# MCU.net
KiCad netlist of a schematic drawn in Altium Designer
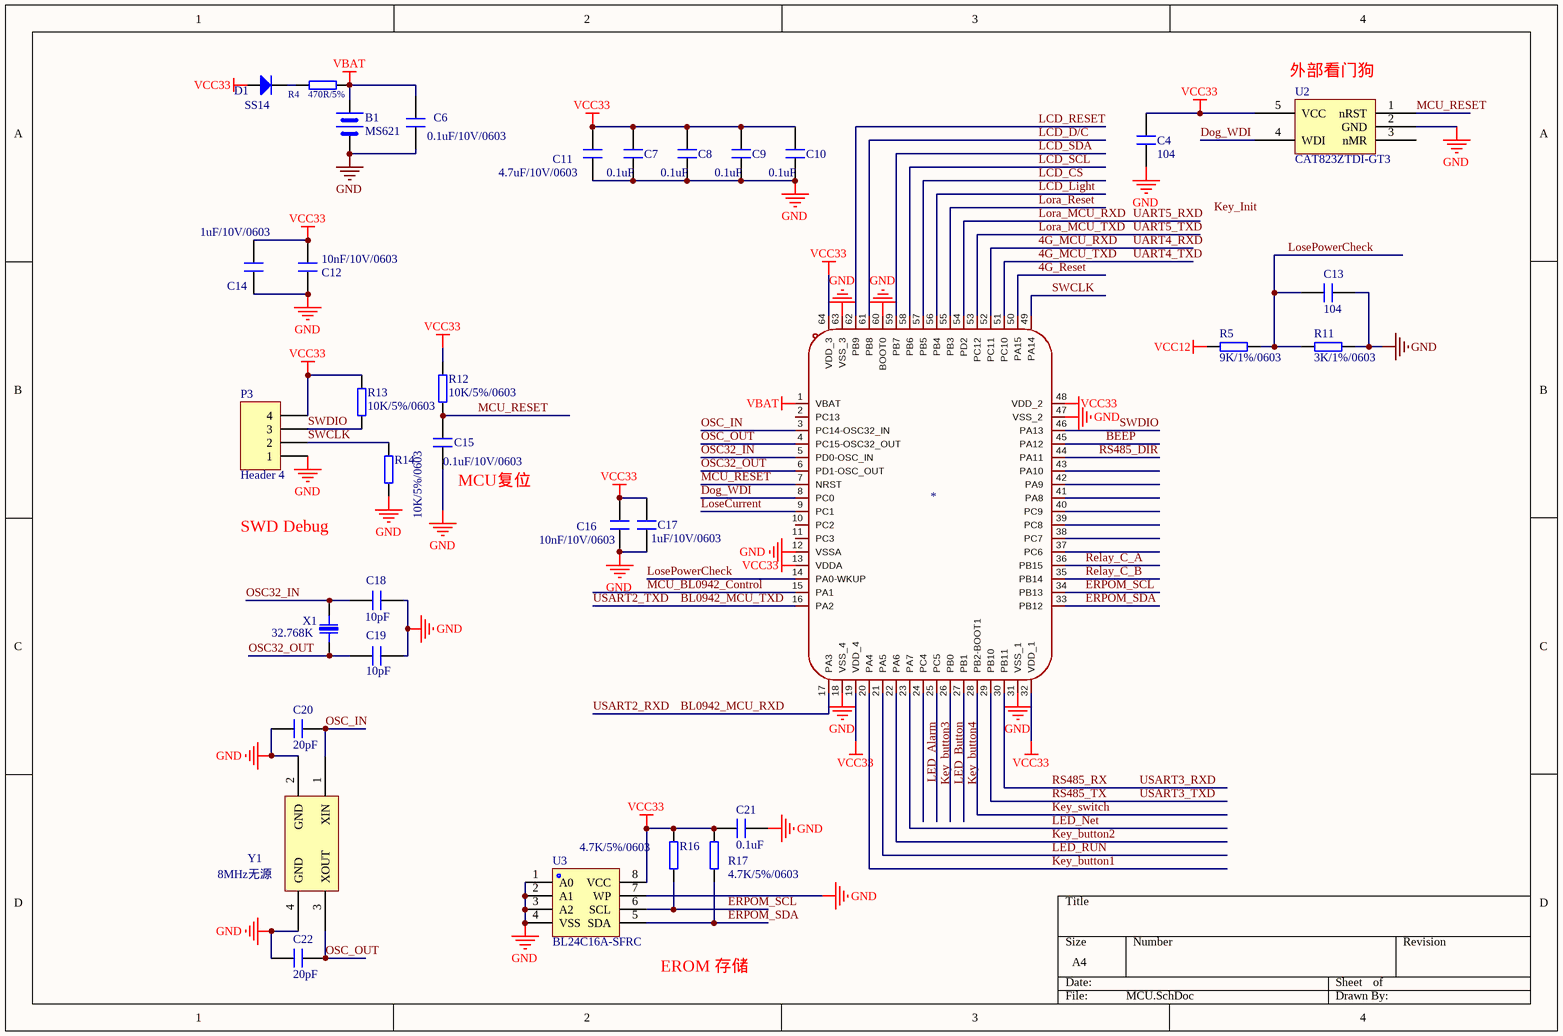
[diagram p0: MCU.SchDoc]

(export (version "E")
  (design (tool "Eeschema 10.0.6"))
  (components
    (comp (ref "B1") (value "MS621") (footprint "MS621") (libsource (lib "ES_Schematic") (part "BATTERY")))
    (comp (ref "C4") (value "104") (footprint "0603R") (libsource (lib "ES_Schematic") (part "CAP")))
    (comp (ref "C6")
      (value "0.1uF/10V/0603")
      (footprint "0603R")
      (libsource (lib "ES_Schematic") (part "CAP_1"))
    )
    (comp (ref "C7") (value "0.1uF") (footprint "0603R") (libsource (lib "ES_Schematic") (part "CAP_1")))
    (comp (ref "C8") (value "0.1uF") (footprint "0603R") (libsource (lib "ES_Schematic") (part "CAP_1")))
    (comp (ref "C9") (value "0.1uF") (footprint "0603R") (libsource (lib "ES_Schematic") (part "CAP_1")))
    (comp (ref "C10") (value "0.1uF") (footprint "0603R") (libsource (lib "ES_Schematic") (part "CAP_1")))
    (comp (ref "C11")
      (value "4.7uF/10V/0603")
      (footprint "0603R")
      (libsource (lib "ES_Schematic") (part "CAP_1"))
    )
    (comp (ref "C12")
      (value "10nF/10V/0603")
      (footprint "0603R")
      (libsource (lib "ES_Schematic") (part "CAP_1"))
    )
    (comp (ref "C13") (value "104") (footprint "0603R") (libsource (lib "ES_Schematic") (part "CAP")))
    (comp (ref "C14")
      (value "1uF/10V/0603")
      (footprint "0603R")
      (libsource (lib "ES_Schematic") (part "CAP_1"))
    )
    (comp (ref "C15")
      (value "0.1uF/10V/0603")
      (footprint "0603R")
      (libsource (lib "ES_Schematic") (part "CAP_1"))
    )
    (comp (ref "C16")
      (value "10nF/10V/0603")
      (footprint "0603R")
      (libsource (lib "ES_Schematic") (part "CAP_1"))
    )
    (comp (ref "C17")
      (value "1uF/10V/0603")
      (footprint "0603R")
      (libsource (lib "ES_Schematic") (part "CAP_1"))
    )
    (comp (ref "C18") (value "10pF") (footprint "0603r") (libsource (lib "ES_Schematic") (part "CAP")))
    (comp (ref "C19") (value "10pF") (footprint "0603r") (libsource (lib "ES_Schematic") (part "CAP")))
    (comp (ref "C20") (value "20pF") (footprint "0603r") (libsource (lib "ES_Schematic") (part "CAP")))
    (comp (ref "C21") (value "0.1uF") (footprint "0603R") (libsource (lib "ES_Schematic") (part "CAP_1")))
    (comp (ref "C22") (value "20pF") (footprint "0603r") (libsource (lib "ES_Schematic") (part "CAP")))
    (comp (ref "D1") (value "SS14") (footprint "SOD323") (libsource (lib "ES_Schematic") (part "DIODE")))
    (comp (ref "P3")
      (value "Header 4")
      (footprint "HDR1X4")
      (description "Header, 4-Pin")
      (fields (field (name "PUBLISHER") "Altium Limited"))
      (libsource (lib "Miscellaneous Connectors") (part "Header 4"))
    )
    (comp (ref "R4") (value "470R/5%") (footprint "0603R") (libsource (lib "ES_Schematic") (part "RES")))
    (comp (ref "R5") (value "9K/1%/0603") (footprint "0603R") (libsource (lib "ES_Schematic") (part "RES")))
    (comp (ref "R11") (value "3K/1%/0603") (footprint "0603R") (libsource (lib "ES_Schematic") (part "RES")))
    (comp (ref "R12") (value "10K/5%/0603") (footprint "0603r") (libsource (lib "ES_Schematic") (part "RES")))
    (comp (ref "R13") (value "10K/5%/0603") (footprint "0603r") (libsource (lib "ES_Schematic") (part "RES")))
    (comp (ref "R14") (value "10K/5%/0603") (footprint "0603r") (libsource (lib "ES_Schematic") (part "RES")))
    (comp (ref "R16")
      (value "4.7K/5%/0603")
      (footprint "0603R")
      (libsource (lib "ES_Schematic") (part "RES"))
    )
    (comp (ref "R17")
      (value "4.7K/5%/0603")
      (footprint "0603R")
      (libsource (lib "ES_Schematic") (part "RES"))
    )
    (comp (ref "U1")
      (value "*")
      (footprint "LQFP64")
      (libsource (lib "altium-import") (part "root_0_N32G452REL7_"))
    )
    (comp (ref "U2")
      (value "CAT823ZTDI-GT3")
      (footprint "SOT-23-5")
      (libsource (lib "ES_Schematic") (part "CAT823"))
    )
    (comp (ref "U3")
      (value "BL24C16A-SFRC")
      (footprint "TSSOP8")
      (libsource (lib "ES_Schematic") (part "24LC02"))
    )
    (comp (ref "X1")
      (value "32.768K")
      (footprint "无源32.768K晶振圆柱")
      (libsource (lib "ES_Schematic") (part "XTAL"))
    )
    (comp (ref "Y1") (value "8MHz无源") (footprint "3225") (libsource (lib "others") (part "12MHz无源")))
  )
  (nets
    (net (code "1") (name "/4G_MCU_RXD") (class "Default")
      (node (ref "U1") (pin "52") (pinfunction "PC11_52") (pintype "passive"))
    )
    (net (code "2") (name "/4G_MCU_TXD") (class "Default")
      (node (ref "U1") (pin "51") (pinfunction "PC10_51") (pintype "passive"))
    )
    (net (code "3") (name "/4G_Reset") (class "Default")
      (node (ref "U1") (pin "50") (pinfunction "PA15_50") (pintype "passive"))
    )
    (net (code "4") (name "/BEEP") (class "Default")
      (node (ref "U1") (pin "45") (pinfunction "PA12_45") (pintype "passive"))
    )
    (net (code "5") (name "/BL0942_MCU_RXD") (class "Default")
      (node (ref "U1") (pin "17") (pinfunction "PA3_17") (pintype "passive"))
    )
    (net (code "6") (name "/BL0942_MCU_TXD") (class "Default")
      (node (ref "U1") (pin "16") (pinfunction "PA2_16") (pintype "passive"))
    )
    (net (code "7") (name "/Dog_WDI") (class "Default")
      (node (ref "U1") (pin "8") (pinfunction "PC0_8") (pintype "passive"))
      (node (ref "U2") (pin "4") (pinfunction "WDI_4") (pintype "passive"))
    )
    (net (code "8") (name "/ERPOM_SCL") (class "Default")
      (node (ref "R16") (pin "2") (pinfunction "2_2") (pintype "passive"))
      (node (ref "U1") (pin "34") (pinfunction "PB13_34") (pintype "passive"))
      (node (ref "U3") (pin "6") (pinfunction "SCL_6") (pintype "passive"))
    )
    (net (code "9") (name "/ERPOM_SDA") (class "Default")
      (node (ref "R17") (pin "2") (pinfunction "2_2") (pintype "passive"))
      (node (ref "U1") (pin "33") (pinfunction "PB12_33") (pintype "passive"))
      (node (ref "U3") (pin "5") (pinfunction "SDA_5") (pintype "passive"))
    )
    (net (code "11") (name "/Key_button1") (class "Default")
      (node (ref "U1") (pin "20") (pinfunction "PA4_20") (pintype "passive"))
    )
    (net (code "12") (name "/Key_button2") (class "Default")
      (node (ref "U1") (pin "22") (pinfunction "PA6_22") (pintype "passive"))
    )
    (net (code "13") (name "/Key_button3") (class "Default")
      (node (ref "U1") (pin "25") (pinfunction "PC5_25") (pintype "passive"))
    )
    (net (code "14") (name "/Key_button4") (class "Default")
      (node (ref "U1") (pin "27") (pinfunction "PB1_27") (pintype "passive"))
    )
    (net (code "15") (name "/Key_switch") (class "Default")
      (node (ref "U1") (pin "28") (pinfunction "PB2-BOOT1_28") (pintype "passive"))
    )
    (net (code "16") (name "/LCD_CS") (class "Default")
      (node (ref "U1") (pin "57") (pinfunction "PB5_57") (pintype "passive"))
    )
    (net (code "17") (name "/LCD_D{slash}C") (class "Default")
      (node (ref "U1") (pin "61") (pinfunction "PB8_61") (pintype "passive"))
    )
    (net (code "18") (name "/LCD_Light") (class "Default")
      (node (ref "U1") (pin "56") (pinfunction "PB4_56") (pintype "passive"))
    )
    (net (code "19") (name "/LCD_RESET") (class "Default")
      (node (ref "U1") (pin "62") (pinfunction "PB9_62") (pintype "passive"))
    )
    (net (code "20") (name "/LCD_SCL") (class "Default")
      (node (ref "U1") (pin "58") (pinfunction "PB6_58") (pintype "passive"))
    )
    (net (code "21") (name "/LCD_SDA") (class "Default")
      (node (ref "U1") (pin "59") (pinfunction "PB7_59") (pintype "passive"))
    )
    (net (code "22") (name "/LED_Alarm") (class "Default")
      (node (ref "U1") (pin "24") (pinfunction "PC4_24") (pintype "passive"))
    )
    (net (code "23") (name "/LED_Button") (class "Default")
      (node (ref "U1") (pin "26") (pinfunction "PB0_26") (pintype "passive"))
    )
    (net (code "24") (name "/LED_Net") (class "Default")
      (node (ref "U1") (pin "23") (pinfunction "PA7_23") (pintype "passive"))
    )
    (net (code "25") (name "/LED_RUN") (class "Default")
      (node (ref "U1") (pin "21") (pinfunction "PA5_21") (pintype "passive"))
    )
    (net (code "26") (name "/Lora_MCU_RXD") (class "Default")
      (node (ref "U1") (pin "54") (pinfunction "PD2_54") (pintype "passive"))
    )
    (net (code "27") (name "/Lora_MCU_TXD") (class "Default")
      (node (ref "U1") (pin "53") (pinfunction "PC12_53") (pintype "passive"))
    )
    (net (code "28") (name "/Lora_Reset") (class "Default")
      (node (ref "U1") (pin "55") (pinfunction "PB3_55") (pintype "passive"))
    )
    (net (code "29") (name "/LoseCurrent") (class "Default")
      (node (ref "U1") (pin "9") (pinfunction "PC1_9") (pintype "passive"))
    )
    (net (code "30") (name "/LosePowerCheck") (class "Default")
      (node (ref "C13") (pin "2") (pinfunction "2_2") (pintype "passive"))
      (node (ref "R11") (pin "2") (pinfunction "2_2") (pintype "passive"))
      (node (ref "R5") (pin "2") (pinfunction "2_2") (pintype "passive"))
      (node (ref "U1") (pin "14") (pinfunction "PA0-WKUP_14") (pintype "passive"))
    )
    (net (code "31") (name "/MCU_BL0942_Control") (class "Default")
      (node (ref "U1") (pin "15") (pinfunction "PA1_15") (pintype "passive"))
    )
    (net (code "32") (name "/MCU_RESET") (class "Default")
      (node (ref "C15") (pin "2") (pinfunction "2_2") (pintype "passive"))
      (node (ref "R12") (pin "1") (pinfunction "1_1") (pintype "passive"))
      (node (ref "U1") (pin "7") (pinfunction "NRST_7") (pintype "passive"))
      (node (ref "U2") (pin "1") (pinfunction "nRST_1") (pintype "passive"))
    )
    (net (code "33") (name "/OSC32_IN") (class "Default")
      (node (ref "C18") (pin "1") (pinfunction "1_1") (pintype "passive"))
      (node (ref "U1") (pin "5") (pinfunction "PD0-OSC_IN_5") (pintype "passive"))
      (node (ref "X1") (pin "2") (pinfunction "2_2") (pintype "passive"))
    )
    (net (code "34") (name "/OSC32_OUT") (class "Default")
      (node (ref "C19") (pin "2") (pinfunction "2_2") (pintype "passive"))
      (node (ref "U1") (pin "6") (pinfunction "PD1-OSC_OUT_6") (pintype "passive"))
      (node (ref "X1") (pin "1") (pinfunction "1_1") (pintype "passive"))
    )
    (net (code "35") (name "/OSC_IN") (class "Default")
      (node (ref "C20") (pin "2") (pinfunction "2_2") (pintype "passive"))
      (node (ref "U1") (pin "3") (pinfunction "PC14-OSC32_IN_3") (pintype "passive"))
      (node (ref "Y1") (pin "1") (pinfunction "XIN_1") (pintype "passive"))
    )
    (net (code "36") (name "/OSC_OUT") (class "Default")
      (node (ref "C22") (pin "2") (pinfunction "2_2") (pintype "passive"))
      (node (ref "U1") (pin "4") (pinfunction "PC15-OSC32_OUT_4") (pintype "passive"))
      (node (ref "Y1") (pin "3") (pinfunction "XOUT_3") (pintype "passive"))
    )
    (net (code "37") (name "/RS485_DIR") (class "Default")
      (node (ref "U1") (pin "44") (pinfunction "PA11_44") (pintype "passive"))
    )
    (net (code "38") (name "/RS485_RX") (class "Default")
      (node (ref "U1") (pin "30") (pinfunction "PB11_30") (pintype "passive"))
    )
    (net (code "39") (name "/RS485_TX") (class "Default")
      (node (ref "U1") (pin "29") (pinfunction "PB10_29") (pintype "passive"))
    )
    (net (code "40") (name "/Relay_C_A") (class "Default")
      (node (ref "U1") (pin "36") (pinfunction "PB15_36") (pintype "passive"))
    )
    (net (code "41") (name "/Relay_C_B") (class "Default")
      (node (ref "U1") (pin "35") (pinfunction "PB14_35") (pintype "passive"))
    )
    (net (code "42") (name "/SWCLK") (class "Default")
      (node (ref "P3") (pin "2") (pinfunction "2_2") (pintype "passive"))
      (node (ref "R14") (pin "2") (pinfunction "2_2") (pintype "passive"))
      (node (ref "U1") (pin "49") (pinfunction "PA14_49") (pintype "passive"))
    )
    (net (code "43") (name "/SWDIO") (class "Default")
      (node (ref "P3") (pin "3") (pinfunction "3_3") (pintype "passive"))
      (node (ref "R13") (pin "1") (pinfunction "1_1") (pintype "passive"))
      (node (ref "U1") (pin "46") (pinfunction "PA13_46") (pintype "passive"))
    )
    (net (code "44") (name "GND") (class "Default")
      (node (ref "B1") (pin "2") (pinfunction "2_2") (pintype "passive"))
      (node (ref "C10") (pin "1") (pinfunction "1_1") (pintype "passive"))
      (node (ref "C11") (pin "1") (pinfunction "1_1") (pintype "passive"))
      (node (ref "C12") (pin "1") (pinfunction "1_1") (pintype "passive"))
      (node (ref "C13") (pin "1") (pinfunction "1_1") (pintype "passive"))
      (node (ref "C14") (pin "1") (pinfunction "1_1") (pintype "passive"))
      (node (ref "C15") (pin "1") (pinfunction "1_1") (pintype "passive"))
      (node (ref "C16") (pin "1") (pinfunction "1_1") (pintype "passive"))
      (node (ref "C17") (pin "1") (pinfunction "1_1") (pintype "passive"))
      (node (ref "C18") (pin "2") (pinfunction "2_2") (pintype "passive"))
      (node (ref "C19") (pin "1") (pinfunction "1_1") (pintype "passive"))
      (node (ref "C20") (pin "1") (pinfunction "1_1") (pintype "passive"))
      (node (ref "C21") (pin "1") (pinfunction "1_1") (pintype "passive"))
      (node (ref "C22") (pin "1") (pinfunction "1_1") (pintype "passive"))
      (node (ref "C4") (pin "1") (pinfunction "1_1") (pintype "passive"))
      (node (ref "C6") (pin "1") (pinfunction "1_1") (pintype "passive"))
      (node (ref "C7") (pin "1") (pinfunction "1_1") (pintype "passive"))
      (node (ref "C8") (pin "1") (pinfunction "1_1") (pintype "passive"))
      (node (ref "C9") (pin "1") (pinfunction "1_1") (pintype "passive"))
      (node (ref "P3") (pin "1") (pinfunction "1_1") (pintype "passive"))
      (node (ref "R11") (pin "1") (pinfunction "1_1") (pintype "passive"))
      (node (ref "R14") (pin "1") (pinfunction "1_1") (pintype "passive"))
      (node (ref "U1") (pin "12") (pinfunction "VSSA_12") (pintype "passive"))
      (node (ref "U1") (pin "18") (pinfunction "VSS_4_18") (pintype "passive"))
      (node (ref "U1") (pin "31") (pinfunction "VSS_1_31") (pintype "passive"))
      (node (ref "U1") (pin "47") (pinfunction "VSS_2_47") (pintype "passive"))
      (node (ref "U1") (pin "60") (pinfunction "BOOT0_60") (pintype "passive"))
      (node (ref "U1") (pin "63") (pinfunction "VSS_3_63") (pintype "passive"))
      (node (ref "U2") (pin "2") (pinfunction "GND_2") (pintype "passive"))
      (node (ref "U3") (pin "1") (pinfunction "A0_1") (pintype "passive"))
      (node (ref "U3") (pin "2") (pinfunction "A1_2") (pintype "passive"))
      (node (ref "U3") (pin "3") (pinfunction "A2_3") (pintype "passive"))
      (node (ref "U3") (pin "4") (pinfunction "VSS_4") (pintype "passive"))
      (node (ref "U3") (pin "7") (pinfunction "WP_7") (pintype "passive"))
      (node (ref "Y1") (pin "2") (pinfunction "GND_2") (pintype "passive"))
      (node (ref "Y1") (pin "4") (pinfunction "GND_4") (pintype "passive"))
    )
    (net (code "45") (name "Net-(D1-K)") (class "Default")
      (node (ref "D1") (pin "1") (pinfunction "K_1") (pintype "passive"))
      (node (ref "R4") (pin "2") (pinfunction "2_2") (pintype "passive"))
    )
    (net (code "46") (name "VBAT") (class "Default")
      (node (ref "B1") (pin "1") (pinfunction "1_1") (pintype "passive"))
      (node (ref "C6") (pin "2") (pinfunction "2_2") (pintype "passive"))
      (node (ref "R4") (pin "1") (pinfunction "1_1") (pintype "passive"))
      (node (ref "U1") (pin "1") (pinfunction "VBAT_1") (pintype "passive"))
    )
    (net (code "47") (name "VCC12") (class "Default")
      (node (ref "R5") (pin "1") (pinfunction "1_1") (pintype "passive"))
    )
    (net (code "48") (name "VCC33") (class "Default")
      (node (ref "C10") (pin "2") (pinfunction "2_2") (pintype "passive"))
      (node (ref "C11") (pin "2") (pinfunction "2_2") (pintype "passive"))
      (node (ref "C12") (pin "2") (pinfunction "2_2") (pintype "passive"))
      (node (ref "C14") (pin "2") (pinfunction "2_2") (pintype "passive"))
      (node (ref "C16") (pin "2") (pinfunction "2_2") (pintype "passive"))
      (node (ref "C17") (pin "2") (pinfunction "2_2") (pintype "passive"))
      (node (ref "C21") (pin "2") (pinfunction "2_2") (pintype "passive"))
      (node (ref "C4") (pin "2") (pinfunction "2_2") (pintype "passive"))
      (node (ref "C7") (pin "2") (pinfunction "2_2") (pintype "passive"))
      (node (ref "C8") (pin "2") (pinfunction "2_2") (pintype "passive"))
      (node (ref "C9") (pin "2") (pinfunction "2_2") (pintype "passive"))
      (node (ref "D1") (pin "2") (pinfunction "A_2") (pintype "passive"))
      (node (ref "P3") (pin "4") (pinfunction "4_4") (pintype "passive"))
      (node (ref "R12") (pin "2") (pinfunction "2_2") (pintype "passive"))
      (node (ref "R13") (pin "2") (pinfunction "2_2") (pintype "passive"))
      (node (ref "R16") (pin "1") (pinfunction "1_1") (pintype "passive"))
      (node (ref "R17") (pin "1") (pinfunction "1_1") (pintype "passive"))
      (node (ref "U1") (pin "13") (pinfunction "VDDA_13") (pintype "passive"))
      (node (ref "U1") (pin "19") (pinfunction "VDD_4_19") (pintype "passive"))
      (node (ref "U1") (pin "32") (pinfunction "VDD_1_32") (pintype "passive"))
      (node (ref "U1") (pin "48") (pinfunction "VDD_2_48") (pintype "passive"))
      (node (ref "U1") (pin "64") (pinfunction "VDD_3_64") (pintype "passive"))
      (node (ref "U2") (pin "5") (pinfunction "VCC_5") (pintype "passive"))
      (node (ref "U3") (pin "8") (pinfunction "VCC_8") (pintype "passive"))
    )
    (net (code "49") (name "unconnected-(U1-PA8-Pad41)") (class "Default")
      (node (ref "U1") (pin "41") (pinfunction "PA8_41") (pintype "passive"))
    )
    (net (code "50") (name "unconnected-(U1-PA9-Pad42)") (class "Default")
      (node (ref "U1") (pin "42") (pinfunction "PA9_42") (pintype "passive"))
    )
    (net (code "51") (name "unconnected-(U1-PA10-Pad43)") (class "Default")
      (node (ref "U1") (pin "43") (pinfunction "PA10_43") (pintype "passive"))
    )
    (net (code "52") (name "unconnected-(U1-PC2-Pad10)") (class "Default")
      (node (ref "U1") (pin "10") (pinfunction "PC2_10") (pintype "passive"))
    )
    (net (code "53") (name "unconnected-(U1-PC3-Pad11)") (class "Default")
      (node (ref "U1") (pin "11") (pinfunction "PC3_11") (pintype "passive"))
    )
    (net (code "54") (name "unconnected-(U1-PC6-Pad37)") (class "Default")
      (node (ref "U1") (pin "37") (pinfunction "PC6_37") (pintype "passive"))
    )
    (net (code "55") (name "unconnected-(U1-PC7-Pad38)") (class "Default")
      (node (ref "U1") (pin "38") (pinfunction "PC7_38") (pintype "passive"))
    )
    (net (code "56") (name "unconnected-(U1-PC8-Pad39)") (class "Default")
      (node (ref "U1") (pin "39") (pinfunction "PC8_39") (pintype "passive"))
    )
    (net (code "57") (name "unconnected-(U1-PC9-Pad40)") (class "Default")
      (node (ref "U1") (pin "40") (pinfunction "PC9_40") (pintype "passive"))
    )
    (net (code "58") (name "unconnected-(U1-PC13-Pad2)") (class "Default")
      (node (ref "U1") (pin "2") (pinfunction "PC13_2") (pintype "passive"))
    )
    (net (code "59") (name "unconnected-(U2-nMR-Pad3)") (class "Default")
      (node (ref "U2") (pin "3") (pinfunction "nMR_3") (pintype "passive"))
    )
  )
)
